# SAM_E54_Xplained_Pro_Memory.net
KiCad netlist of a schematic drawn in Altium Designer
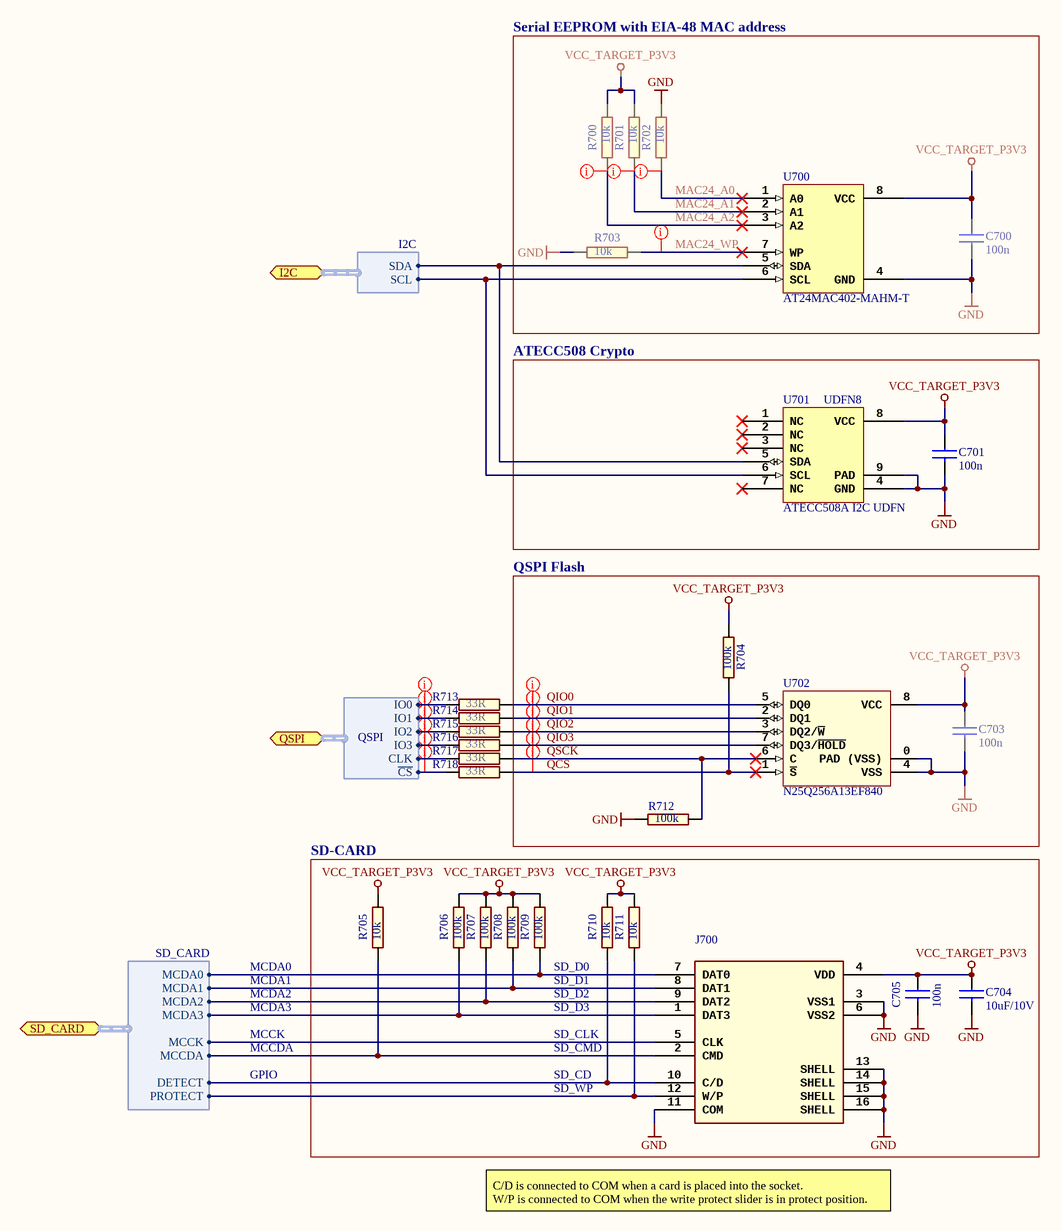
[diagram p0: SAM_E54_Xplained_Pro_Memory.SchDoc]

(export (version "E")
  (design (tool "Eeschema 10.0.6"))
  (components
    (comp (ref "C700")
      (value "100n")
      (footprint "AP1-00053")
      (description "Ceramic capacitor, SMD 0402, X7R, 16V, +/-10%")
      (fields (field (name "TOLERANCE") "16V, +/-10%") (field (name "MANUFACTURER") "Kemet"))
      (libsource (lib "AltiumDbLib") (part "CAP-NONPOL"))
    )
    (comp (ref "C701")
      (value "100n")
      (footprint "AP1-00053")
      (description "Ceramic capacitor, SMD 0402, X7R, 16V, +/-10%")
      (fields (field (name "TOLERANCE") "16V, +/-10%") (field (name "MANUFACTURER") "Kemet"))
      (libsource (lib "AltiumDbLib") (part "CAP-NONPOL"))
    )
    (comp (ref "C703")
      (value "100n")
      (footprint "AP1-00053")
      (description "Ceramic capacitor, SMD 0402, X7R, 16V, +/-10%")
      (fields (field (name "TOLERANCE") "16V, +/-10%") (field (name "MANUFACTURER") "Kemet"))
      (libsource (lib "AltiumDbLib") (part "CAP-NONPOL"))
    )
    (comp (ref "C704")
      (value "10uF/10V")
      (footprint "AP1-00117")
      (description "Ceramic capacitor, SMD 0603, X5R, 10V, 10UF Â± 20%")
      (fields (field (name "MANUFACTURER") "AVX") (field (name "MPN") "0603ZD106MAT2A"))
      (libsource (lib "AltiumDbLib") (part "CAP-NONPOL"))
    )
    (comp (ref "C705")
      (value "100n")
      (footprint "AP1-00053")
      (description "Ceramic capacitor, SMD 0402, X7R, 16V, +/-10%")
      (fields (field (name "TOLERANCE") "16V, +/-10%") (field (name "MANUFACTURER") "Kemet"))
      (libsource (lib "AltiumDbLib") (part "CAP-NONPOL"))
    )
    (comp (ref "J700")
      (value "~")
      (footprint "AP8-00377")
      (description "SD/MMC socket, 2.7mm, push-push, SMD")
      (fields
        (field (name "MANUFACTURER") "Kyocera-elco")
        (field (name "MPN") "KYOCERA - 14 5738 009 220 859+")
      )
      (libsource (lib "AltiumDbLib") (part "SD_MMC"))
    )
    (comp (ref "R700")
      (value "10k")
      (footprint "AP2-00011")
      (description "Thick film resistor, SMD 0402, 1/16W, 1%")
      (fields (field (name "TOLERANCE") "1 %") (field (name "MANUFACTURER") "vishay"))
      (libsource (lib "AltiumDbLib") (part "R2"))
    )
    (comp (ref "R701")
      (value "10k")
      (footprint "AP2-00011")
      (description "Thick film resistor, SMD 0402, 1/16W, 1%")
      (fields (field (name "TOLERANCE") "1 %") (field (name "MANUFACTURER") "vishay"))
      (libsource (lib "AltiumDbLib") (part "R2"))
    )
    (comp (ref "R702")
      (value "10k")
      (footprint "AP2-00011")
      (description "Thick film resistor, SMD 0402, 1/16W, 1%")
      (fields (field (name "TOLERANCE") "1 %") (field (name "MANUFACTURER") "vishay"))
      (libsource (lib "AltiumDbLib") (part "R2"))
    )
    (comp (ref "R703")
      (value "10k")
      (footprint "AP2-00011")
      (description "Thick film resistor, SMD 0402, 1/16W, 1%")
      (fields (field (name "TOLERANCE") "1 %") (field (name "MANUFACTURER") "vishay"))
      (libsource (lib "") (part "R2_1"))
    )
    (comp (ref "R704")
      (value "100k")
      (footprint "AP2-00011")
      (description "Thick film resistor, SMD 0402, 1/16W, 1%")
      (fields (field (name "TOLERANCE") "1 %") (field (name "MANUFACTURER") "ASJ"))
      (libsource (lib "AltiumDbLib") (part "R2"))
    )
    (comp (ref "R705")
      (value "10k")
      (footprint "AP2-00011")
      (description "Thick film resistor, SMD 0402, 1/16W, 1%")
      (fields (field (name "TOLERANCE") "1 %") (field (name "MANUFACTURER") "vishay"))
      (libsource (lib "AltiumDbLib") (part "R2"))
    )
    (comp (ref "R706")
      (value "100k")
      (footprint "AP2-00011")
      (description "Thick film resistor, SMD 0402, 1/16W, 1%")
      (fields (field (name "TOLERANCE") "1 %") (field (name "MANUFACTURER") "ASJ"))
      (libsource (lib "AltiumDbLib") (part "R2"))
    )
    (comp (ref "R707")
      (value "100k")
      (footprint "AP2-00011")
      (description "Thick film resistor, SMD 0402, 1/16W, 1%")
      (fields (field (name "TOLERANCE") "1 %") (field (name "MANUFACTURER") "ASJ"))
      (libsource (lib "AltiumDbLib") (part "R2"))
    )
    (comp (ref "R708")
      (value "100k")
      (footprint "AP2-00011")
      (description "Thick film resistor, SMD 0402, 1/16W, 1%")
      (fields (field (name "TOLERANCE") "1 %") (field (name "MANUFACTURER") "ASJ"))
      (libsource (lib "AltiumDbLib") (part "R2"))
    )
    (comp (ref "R709")
      (value "100k")
      (footprint "AP2-00011")
      (description "Thick film resistor, SMD 0402, 1/16W, 1%")
      (fields (field (name "TOLERANCE") "1 %") (field (name "MANUFACTURER") "ASJ"))
      (libsource (lib "AltiumDbLib") (part "R2"))
    )
    (comp (ref "R710")
      (value "10k")
      (footprint "AP2-00011")
      (description "Thick film resistor, SMD 0402, 1/16W, 1%")
      (fields (field (name "TOLERANCE") "1 %") (field (name "MANUFACTURER") "vishay"))
      (libsource (lib "AltiumDbLib") (part "R2"))
    )
    (comp (ref "R711")
      (value "10k")
      (footprint "AP2-00011")
      (description "Thick film resistor, SMD 0402, 1/16W, 1%")
      (fields (field (name "TOLERANCE") "1 %") (field (name "MANUFACTURER") "vishay"))
      (libsource (lib "AltiumDbLib") (part "R2"))
    )
    (comp (ref "R712")
      (value "100k")
      (footprint "AP2-00011")
      (description "Thick film resistor, SMD 0402, 1/16W, 1%")
      (fields (field (name "TOLERANCE") "1 %") (field (name "MANUFACTURER") "ASJ"))
      (libsource (lib "") (part "R2_1"))
    )
    (comp (ref "R713")
      (value "33R")
      (footprint "AP2-00011")
      (description "Thick film resistor, SMD 0402, 1/16W, 1%")
      (fields (field (name "TOLERANCE") "1 %") (field (name "MANUFACTURER") "ASJ"))
      (libsource (lib "") (part "R2_2"))
    )
    (comp (ref "R714")
      (value "33R")
      (footprint "AP2-00011")
      (description "Thick film resistor, SMD 0402, 1/16W, 1%")
      (fields (field (name "TOLERANCE") "1 %") (field (name "MANUFACTURER") "ASJ"))
      (libsource (lib "") (part "R2_2"))
    )
    (comp (ref "R715")
      (value "33R")
      (footprint "AP2-00011")
      (description "Thick film resistor, SMD 0402, 1/16W, 1%")
      (fields (field (name "TOLERANCE") "1 %") (field (name "MANUFACTURER") "ASJ"))
      (libsource (lib "") (part "R2_2"))
    )
    (comp (ref "R716")
      (value "33R")
      (footprint "AP2-00011")
      (description "Thick film resistor, SMD 0402, 1/16W, 1%")
      (fields (field (name "TOLERANCE") "1 %") (field (name "MANUFACTURER") "ASJ"))
      (libsource (lib "") (part "R2_2"))
    )
    (comp (ref "R717")
      (value "33R")
      (footprint "AP2-00011")
      (description "Thick film resistor, SMD 0402, 1/16W, 1%")
      (fields (field (name "TOLERANCE") "1 %") (field (name "MANUFACTURER") "ASJ"))
      (libsource (lib "") (part "R2_2"))
    )
    (comp (ref "R718")
      (value "33R")
      (footprint "AP2-00011")
      (description "Thick film resistor, SMD 0402, 1/16W, 1%")
      (fields (field (name "TOLERANCE") "1 %") (field (name "MANUFACTURER") "ASJ"))
      (libsource (lib "") (part "R2_2"))
    )
    (comp (ref "U700")
      (value "AT24MAC402-MAHM-T")
      (footprint "AP6-00186")
      (description "2kbit I2C EEPROM, single EUI-48 MAC, 1.7-5.5V, 2x3mm UDFN (8MA2)")
      (fields (field (name "MANUFACTURER") "ATMEL"))
      (libsource (lib "AltiumDbLib") (part "AT24MAC-8PIN"))
    )
    (comp (ref "U701")
      (value "ATECC508A I2C UDFN")
      (footprint "AP6-00409")
      (description "ATECC508A with an I2C Interface and a 8 Pin UDFN Package with Paddle")
      (fields (field (name "MANUFACTURER") "ATMEL") (field (name "MPN") "ATECC508A-MAHDA-T"))
      (libsource (lib "AltiumDbLib") (part "ATECC508A_I2C_UDFN"))
    )
    (comp (ref "U702")
      (value "N25Q256A13EF840")
      (footprint "AP6-00478")
      (description "256 Mbit (32MB) QSPI flash, 3.3V, 108MHz, V-PDFN-8 (8x6mm)")
      (fields (field (name "MANUFACTURER") "Micron") (field (name "MPN") "N25Q256A13EF840F"))
      (libsource (lib "AltiumDbLib") (part "N25Q256A1"))
    )
  )
  (nets
    (net (code "4") (name "/CLK") (class "Default")
      (node (ref "R717") (pin "2") (pinfunction "2_2") (pintype "passive"))
    )
    (net (code "5") (name "/DETECT") (class "Default")
      (node (ref "J700") (pin "10") (pinfunction "C/D_10") (pintype "passive"))
      (node (ref "R710") (pin "1") (pinfunction "1_1") (pintype "passive"))
    )
    (net (code "6") (name "/IO0") (class "Default")
      (node (ref "R713") (pin "2") (pinfunction "2_2") (pintype "passive"))
    )
    (net (code "7") (name "/IO1") (class "Default")
      (node (ref "R714") (pin "2") (pinfunction "2_2") (pintype "passive"))
    )
    (net (code "8") (name "/IO2") (class "Default")
      (node (ref "R715") (pin "2") (pinfunction "2_2") (pintype "passive"))
    )
    (net (code "9") (name "/IO3") (class "Default")
      (node (ref "R716") (pin "2") (pinfunction "2_2") (pintype "passive"))
    )
    (net (code "10") (name "/MAC24_A0") (class "Default")
      (node (ref "R702") (pin "1") (pinfunction "1_1") (pintype "passive"))
      (node (ref "U700") (pin "1") (pinfunction "A0_1") (pintype "input"))
    )
    (net (code "11") (name "/MAC24_A1") (class "Default")
      (node (ref "R701") (pin "1") (pinfunction "1_1") (pintype "passive"))
      (node (ref "U700") (pin "2") (pinfunction "A1_2") (pintype "input"))
    )
    (net (code "12") (name "/MAC24_A2") (class "Default")
      (node (ref "R700") (pin "1") (pinfunction "1_1") (pintype "passive"))
      (node (ref "U700") (pin "3") (pinfunction "A2_3") (pintype "input"))
    )
    (net (code "13") (name "/MAC24_WP") (class "Default")
      (node (ref "R703") (pin "2") (pinfunction "2_2") (pintype "passive"))
      (node (ref "U700") (pin "7") (pinfunction "WP_7") (pintype "input"))
    )
    (net (code "14") (name "/MCCDA") (class "Default")
      (node (ref "J700") (pin "2") (pinfunction "CMD_2") (pintype "passive"))
      (node (ref "R705") (pin "1") (pinfunction "1_1") (pintype "passive"))
    )
    (net (code "15") (name "/MCCK") (class "Default")
      (node (ref "J700") (pin "5") (pinfunction "CLK_5") (pintype "passive"))
    )
    (net (code "16") (name "/MCDA0") (class "Default")
      (node (ref "J700") (pin "7") (pinfunction "DAT0_7") (pintype "passive"))
      (node (ref "R709") (pin "1") (pinfunction "1_1") (pintype "passive"))
    )
    (net (code "17") (name "/MCDA1") (class "Default")
      (node (ref "J700") (pin "8") (pinfunction "DAT1_8") (pintype "passive"))
      (node (ref "R708") (pin "1") (pinfunction "1_1") (pintype "passive"))
    )
    (net (code "18") (name "/MCDA2") (class "Default")
      (node (ref "J700") (pin "9") (pinfunction "DAT2_9") (pintype "passive"))
      (node (ref "R707") (pin "1") (pinfunction "1_1") (pintype "passive"))
    )
    (net (code "19") (name "/MCDA3") (class "Default")
      (node (ref "J700") (pin "1") (pinfunction "DAT3_1") (pintype "passive"))
      (node (ref "R706") (pin "1") (pinfunction "1_1") (pintype "passive"))
    )
    (net (code "20") (name "/PROTECT") (class "Default")
      (node (ref "J700") (pin "12") (pinfunction "W/P_12") (pintype "passive"))
      (node (ref "R711") (pin "1") (pinfunction "1_1") (pintype "passive"))
    )
    (net (code "21") (name "/QCS") (class "Default")
      (node (ref "R704") (pin "1") (pinfunction "1_1") (pintype "passive"))
      (node (ref "R718") (pin "1") (pinfunction "1_1") (pintype "passive"))
      (node (ref "U702") (pin "1") (pinfunction "~{S}_1") (pintype "input"))
    )
    (net (code "22") (name "/QIO0") (class "Default")
      (node (ref "R713") (pin "1") (pinfunction "1_1") (pintype "passive"))
      (node (ref "U702") (pin "5") (pinfunction "DQ0_5") (pintype "bidirectional"))
    )
    (net (code "23") (name "/QIO1") (class "Default")
      (node (ref "R714") (pin "1") (pinfunction "1_1") (pintype "passive"))
      (node (ref "U702") (pin "2") (pinfunction "DQ1_2") (pintype "bidirectional"))
    )
    (net (code "24") (name "/QIO2") (class "Default")
      (node (ref "R715") (pin "1") (pinfunction "1_1") (pintype "passive"))
      (node (ref "U702") (pin "3") (pinfunction "DQ2/~{W}_3") (pintype "bidirectional"))
    )
    (net (code "25") (name "/QIO3") (class "Default")
      (node (ref "R716") (pin "1") (pinfunction "1_1") (pintype "passive"))
      (node (ref "U702") (pin "7") (pinfunction "DQ3/~{HOLD}_7") (pintype "bidirectional"))
    )
    (net (code "26") (name "/QSCK") (class "Default")
      (node (ref "R712") (pin "2") (pinfunction "2_2") (pintype "passive"))
      (node (ref "R717") (pin "1") (pinfunction "1_1") (pintype "passive"))
      (node (ref "U702") (pin "6") (pinfunction "C_6") (pintype "input"))
    )
    (net (code "27") (name "/SCL") (class "Default")
      (node (ref "U700") (pin "6") (pinfunction "SCL_6") (pintype "input"))
      (node (ref "U701") (pin "6") (pinfunction "SCL_6") (pintype "input"))
    )
    (net (code "28") (name "/SDA") (class "Default")
      (node (ref "U700") (pin "5") (pinfunction "SDA_5") (pintype "bidirectional"))
      (node (ref "U701") (pin "5") (pinfunction "SDA_5") (pintype "bidirectional"))
    )
    (net (code "32") (name "/~{CS}") (class "Default")
      (node (ref "R718") (pin "2") (pinfunction "2_2") (pintype "passive"))
    )
    (net (code "33") (name "GND") (class "Default")
      (node (ref "C700") (pin "2") (pinfunction "2_2") (pintype "passive"))
      (node (ref "C701") (pin "2") (pinfunction "2_2") (pintype "passive"))
      (node (ref "C703") (pin "2") (pinfunction "2_2") (pintype "passive"))
      (node (ref "C704") (pin "2") (pinfunction "2_2") (pintype "passive"))
      (node (ref "C705") (pin "2") (pinfunction "2_2") (pintype "passive"))
      (node (ref "J700") (pin "11") (pinfunction "COM_11") (pintype "passive"))
      (node (ref "J700") (pin "13") (pinfunction "SHELL_13") (pintype "passive"))
      (node (ref "J700") (pin "14") (pinfunction "SHELL_14") (pintype "passive"))
      (node (ref "J700") (pin "15") (pinfunction "SHELL_15") (pintype "passive"))
      (node (ref "J700") (pin "16") (pinfunction "SHELL_16") (pintype "passive"))
      (node (ref "J700") (pin "3") (pinfunction "VSS1_3") (pintype "passive"))
      (node (ref "J700") (pin "6") (pinfunction "VSS2_6") (pintype "passive"))
      (node (ref "R702") (pin "2") (pinfunction "2_2") (pintype "passive"))
      (node (ref "R703") (pin "1") (pinfunction "1_1") (pintype "passive"))
      (node (ref "R712") (pin "1") (pinfunction "1_1") (pintype "passive"))
      (node (ref "U700") (pin "4") (pinfunction "GND_4") (pintype "power_in"))
      (node (ref "U701") (pin "4") (pinfunction "GND_4") (pintype "power_in"))
      (node (ref "U701") (pin "9") (pinfunction "PAD_9") (pintype "power_in"))
      (node (ref "U702") (pin "0") (pinfunction "PAD_(VSS)_0") (pintype "power_in"))
      (node (ref "U702") (pin "4") (pinfunction "VSS_4") (pintype "power_in"))
    )
    (net (code "34") (name "VCC_TARGET_P3V3") (class "Default")
      (node (ref "C700") (pin "1") (pinfunction "1_1") (pintype "passive"))
      (node (ref "C701") (pin "1") (pinfunction "1_1") (pintype "passive"))
      (node (ref "C703") (pin "1") (pinfunction "1_1") (pintype "passive"))
      (node (ref "C704") (pin "1") (pinfunction "1_1") (pintype "passive"))
      (node (ref "C705") (pin "1") (pinfunction "1_1") (pintype "passive"))
      (node (ref "J700") (pin "4") (pinfunction "VDD_4") (pintype "passive"))
      (node (ref "R700") (pin "2") (pinfunction "2_2") (pintype "passive"))
      (node (ref "R701") (pin "2") (pinfunction "2_2") (pintype "passive"))
      (node (ref "R704") (pin "2") (pinfunction "2_2") (pintype "passive"))
      (node (ref "R705") (pin "2") (pinfunction "2_2") (pintype "passive"))
      (node (ref "R706") (pin "2") (pinfunction "2_2") (pintype "passive"))
      (node (ref "R707") (pin "2") (pinfunction "2_2") (pintype "passive"))
      (node (ref "R708") (pin "2") (pinfunction "2_2") (pintype "passive"))
      (node (ref "R709") (pin "2") (pinfunction "2_2") (pintype "passive"))
      (node (ref "R710") (pin "2") (pinfunction "2_2") (pintype "passive"))
      (node (ref "R711") (pin "2") (pinfunction "2_2") (pintype "passive"))
      (node (ref "U700") (pin "8") (pinfunction "VCC_8") (pintype "power_in"))
      (node (ref "U701") (pin "8") (pinfunction "VCC_8") (pintype "power_in"))
      (node (ref "U702") (pin "8") (pinfunction "VCC_8") (pintype "power_in"))
    )
    (net (code "35") (name "unconnected-(U701-NC-Pad1)") (class "Default")
      (node (ref "U701") (pin "1") (pinfunction "NC_1") (pintype "passive+no_connect"))
    )
    (net (code "36") (name "unconnected-(U701-NC-Pad2)") (class "Default")
      (node (ref "U701") (pin "2") (pinfunction "NC_2") (pintype "passive+no_connect"))
    )
    (net (code "37") (name "unconnected-(U701-NC-Pad3)") (class "Default")
      (node (ref "U701") (pin "3") (pinfunction "NC_3") (pintype "passive+no_connect"))
    )
    (net (code "38") (name "unconnected-(U701-NC-Pad7)") (class "Default")
      (node (ref "U701") (pin "7") (pinfunction "NC_7") (pintype "passive+no_connect"))
    )
  )
)
